# vds_botboard_revB.net
KiCad netlist of a schematic drawn in EAGLE
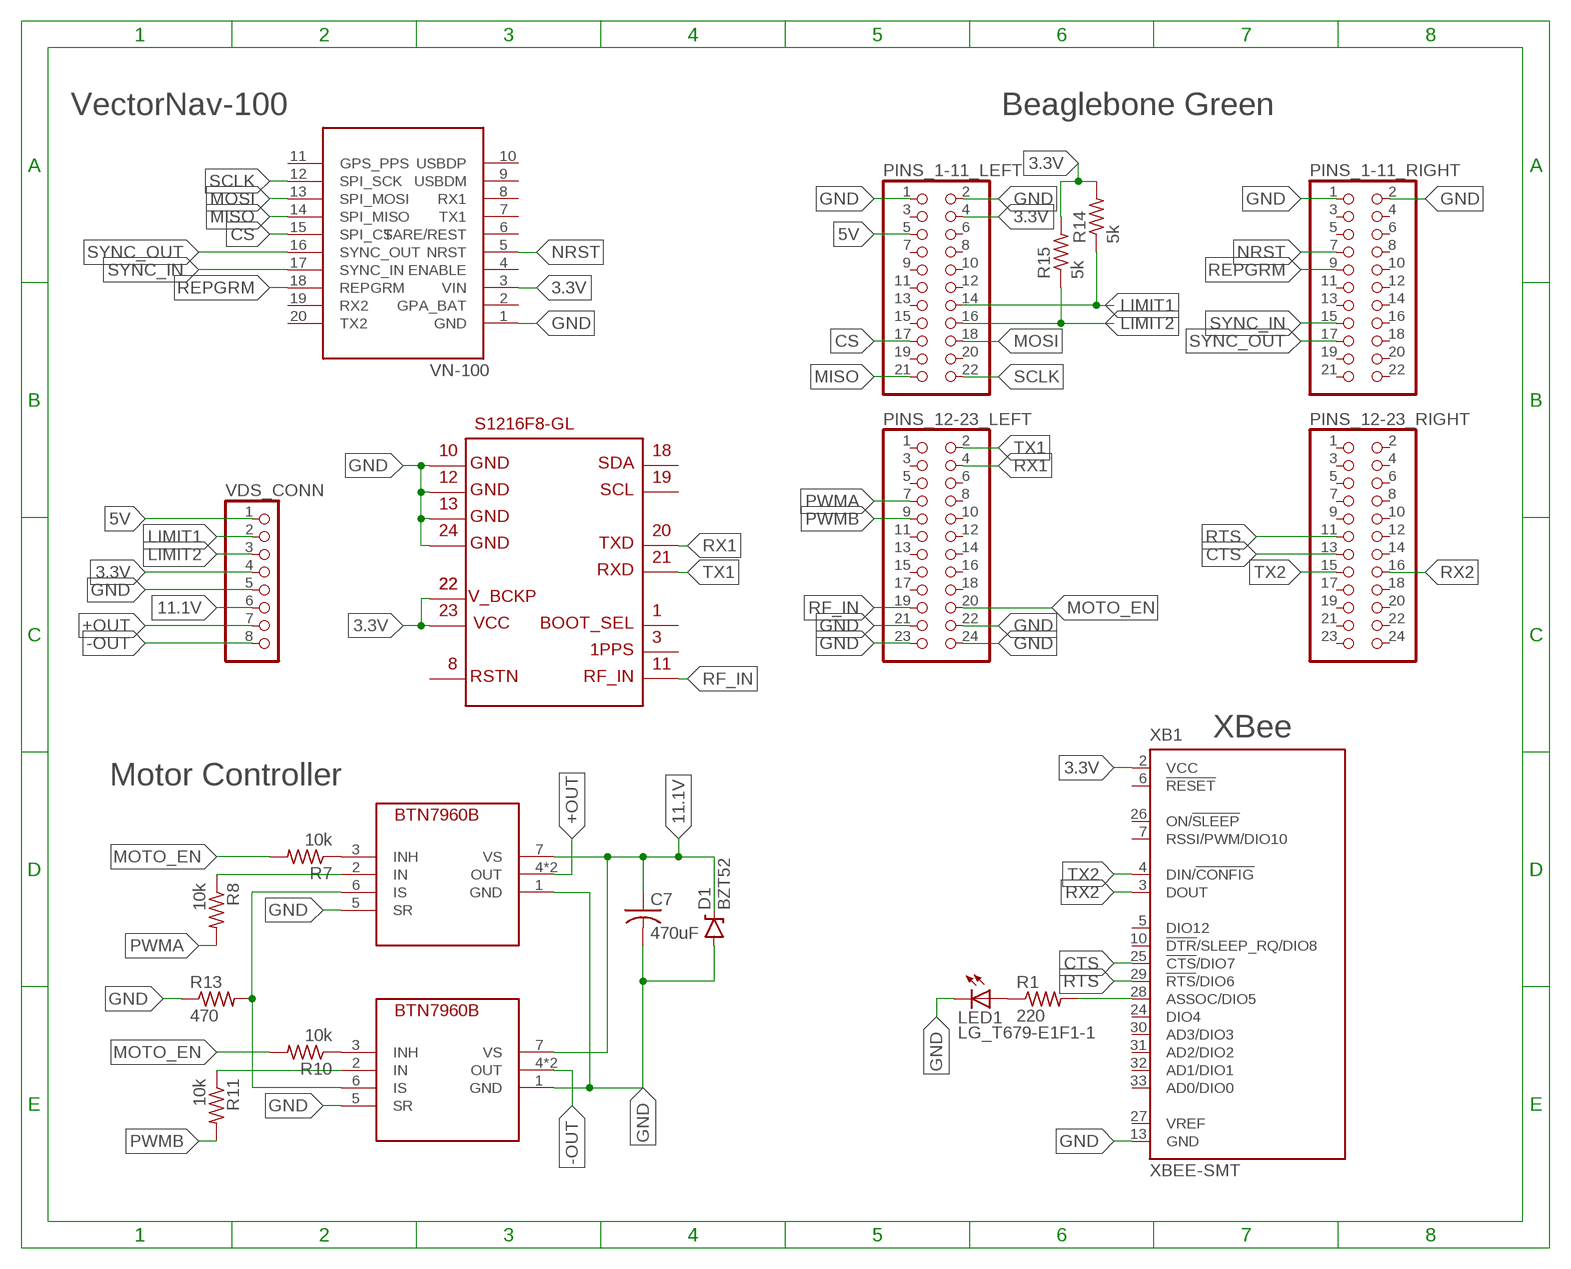
[diagram p0: schematic, sheet 1]

(export (version "E")
  (design (tool "Eeschema 10.0.6"))
  (components
    (comp (ref "C7")
      (value "470uF")
      (footprint "eagle-import:C050-024X044")
      (libsource (lib "eagle-import") (part "C-US050-024X044"))
    )
    (comp (ref "D1")
      (value "BZT52")
      (footprint "eagle-import:DIODE-BZT52")
      (libsource (lib "eagle-import") (part "DIODE-ZENER"))
    )
    (comp (ref "JM1")
      (value "S1216F8-GL")
      (footprint "eagle-import:S1216F8-GL")
      (libsource (lib "eagle-import") (part "S1216F8-GL"))
    )
    (comp (ref "LED1")
      (value "LG_T679-E1F1-1")
      (footprint "eagle-import:PLCC2")
      (libsource (lib "eagle-import") (part "_T679-?-1E1F1LG"))
    )
    (comp (ref "PINS_1-11_LEFT")
      (value "PINHD-2X11")
      (footprint "eagle-import:2X11")
      (libsource (lib "eagle-import") (part "PINHD-2X11"))
    )
    (comp (ref "PINS_1-11_RIGHT")
      (value "PINHD-2X11")
      (footprint "eagle-import:2X11")
      (libsource (lib "eagle-import") (part "PINHD-2X11"))
    )
    (comp (ref "PINS_12-23_LEFT")
      (value "PINHD-2X12")
      (footprint "eagle-import:2X12")
      (libsource (lib "eagle-import") (part "PINHD-2X12"))
    )
    (comp (ref "PINS_12-23_RIGHT")
      (value "PINHD-2X12")
      (footprint "eagle-import:2X12")
      (libsource (lib "eagle-import") (part "PINHD-2X12"))
    )
    (comp (ref "R1")
      (value "220")
      (footprint "eagle-import:0204_5")
      (libsource (lib "eagle-import") (part "resistor_348_R-US_0204/5"))
    )
    (comp (ref "R7")
      (value "10k")
      (footprint "eagle-import:0204_5")
      (libsource (lib "eagle-import") (part "R-US_0204/5"))
    )
    (comp (ref "R8")
      (value "10k")
      (footprint "eagle-import:0204_5")
      (libsource (lib "eagle-import") (part "R-US_0204/5"))
    )
    (comp (ref "R10")
      (value "10k")
      (footprint "eagle-import:0204_5")
      (libsource (lib "eagle-import") (part "R-US_0204/5"))
    )
    (comp (ref "R11")
      (value "10k")
      (footprint "eagle-import:0204_5")
      (libsource (lib "eagle-import") (part "R-US_0204/5"))
    )
    (comp (ref "R13")
      (value "470")
      (footprint "eagle-import:0204_5")
      (libsource (lib "eagle-import") (part "R-US_0204/5"))
    )
    (comp (ref "R14")
      (value "5k")
      (footprint "eagle-import:0204_5")
      (libsource (lib "eagle-import") (part "R-US_0204/5"))
    )
    (comp (ref "R15")
      (value "5k")
      (footprint "eagle-import:0204_5")
      (libsource (lib "eagle-import") (part "R-US_0204/5"))
    )
    (comp (ref "U1")
      (value "INF-PG-TO263-7-1_L_1_BTN7960B")
      (footprint "eagle-import:INF-PG-TO263-7-1_L_1PRIMARY")
      (libsource (lib "eagle-import") (part "INF-PG-TO263-7-1_L_1_BTN7960B"))
    )
    (comp (ref "U2")
      (value "INF-PG-TO263-7-1_L_1_BTN7960B")
      (footprint "eagle-import:INF-PG-TO263-7-1_L_1PRIMARY")
      (libsource (lib "eagle-import") (part "INF-PG-TO263-7-1_L_1_BTN7960B"))
    )
    (comp (ref "VDS_CONN")
      (value "PINHD-1X8")
      (footprint "eagle-import:1X08")
      (libsource (lib "eagle-import") (part "PINHD-1X8"))
    )
    (comp (ref "VN1")
      (value "VECTORNAV-100")
      (footprint "eagle-import:VN-100")
      (libsource (lib "eagle-import") (part "VECTORNAV-100"))
    )
    (comp (ref "XB1")
      (value "XBEE-SMT")
      (footprint "eagle-import:XBEE-SMT")
      (libsource (lib "eagle-import") (part "XBEE-SMT"))
    )
  )
  (nets
    (net (code "1") (name "+OUT") (class "Default")
      (node (ref "U1") (pin "4") (pinfunction "OUT_4") (pintype "bidirectional"))
      (node (ref "U1") (pin "8") (pinfunction "OUT_8") (pintype "bidirectional"))
      (node (ref "VDS_CONN") (pin "7") (pinfunction "7_7") (pintype "passive"))
    )
    (net (code "2") (name "-OUT") (class "Default")
      (node (ref "U2") (pin "4") (pinfunction "OUT_4") (pintype "bidirectional"))
      (node (ref "U2") (pin "8") (pinfunction "OUT_8") (pintype "bidirectional"))
      (node (ref "VDS_CONN") (pin "8") (pinfunction "8_8") (pintype "passive"))
    )
    (net (code "3") (name "3.3V") (class "Default")
      (node (ref "JM1") (pin "22") (pinfunction "22_22") (pintype "bidirectional"))
      (node (ref "JM1") (pin "23") (pinfunction "23_23") (pintype "bidirectional"))
      (node (ref "PINS_1-11_LEFT") (pin "4") (pinfunction "4_4") (pintype "passive"))
      (node (ref "R14") (pin "2") (pinfunction "2_2") (pintype "passive"))
      (node (ref "R15") (pin "2") (pinfunction "2_2") (pintype "passive"))
      (node (ref "VDS_CONN") (pin "4") (pinfunction "4_4") (pintype "passive"))
      (node (ref "VN1") (pin "3") (pinfunction "VIN_3") (pintype "bidirectional"))
      (node (ref "XB1") (pin "2") (pinfunction "VCC_2") (pintype "power_in"))
    )
    (net (code "4") (name "5V") (class "Default")
      (node (ref "PINS_1-11_LEFT") (pin "5") (pinfunction "5_5") (pintype "passive"))
      (node (ref "VDS_CONN") (pin "1") (pinfunction "1_1") (pintype "passive"))
    )
    (net (code "5") (name "11.1V") (class "Default")
      (node (ref "C7") (pin "1") (pinfunction "1_1") (pintype "passive"))
      (node (ref "D1") (pin "C") (pinfunction "C_C") (pintype "passive"))
      (node (ref "U1") (pin "7") (pinfunction "VS_7") (pintype "bidirectional"))
      (node (ref "U2") (pin "7") (pinfunction "VS_7") (pintype "bidirectional"))
      (node (ref "VDS_CONN") (pin "6") (pinfunction "6_6") (pintype "passive"))
    )
    (net (code "6") (name "CS") (class "Default")
      (node (ref "PINS_1-11_LEFT") (pin "17") (pinfunction "17_17") (pintype "passive"))
      (node (ref "VN1") (pin "15") (pinfunction "SPI_CS_15") (pintype "bidirectional"))
    )
    (net (code "7") (name "CTS") (class "Default")
      (node (ref "PINS_12-23_RIGHT") (pin "13") (pinfunction "13_13") (pintype "passive"))
      (node (ref "XB1") (pin "25") (pinfunction "~{CTS}/DIO7_25") (pintype "bidirectional"))
    )
    (net (code "8") (name "GND") (class "Default")
      (node (ref "C7") (pin "2") (pinfunction "2_2") (pintype "passive"))
      (node (ref "D1") (pin "A") (pinfunction "A_A") (pintype "passive"))
      (node (ref "JM1") (pin "10") (pinfunction "10_10") (pintype "bidirectional"))
      (node (ref "JM1") (pin "12") (pinfunction "12_12") (pintype "bidirectional"))
      (node (ref "JM1") (pin "13") (pinfunction "13_13") (pintype "bidirectional"))
      (node (ref "JM1") (pin "24") (pinfunction "24_24") (pintype "bidirectional"))
      (node (ref "LED1") (pin "C") (pinfunction "C_C") (pintype "passive"))
      (node (ref "PINS_1-11_LEFT") (pin "1") (pinfunction "1_1") (pintype "passive"))
      (node (ref "PINS_1-11_LEFT") (pin "2") (pinfunction "2_2") (pintype "passive"))
      (node (ref "PINS_1-11_RIGHT") (pin "1") (pinfunction "1_1") (pintype "passive"))
      (node (ref "PINS_1-11_RIGHT") (pin "2") (pinfunction "2_2") (pintype "passive"))
      (node (ref "PINS_12-23_LEFT") (pin "21") (pinfunction "21_21") (pintype "passive"))
      (node (ref "PINS_12-23_LEFT") (pin "22") (pinfunction "22_22") (pintype "passive"))
      (node (ref "PINS_12-23_LEFT") (pin "23") (pinfunction "23_23") (pintype "passive"))
      (node (ref "PINS_12-23_LEFT") (pin "24") (pinfunction "24_24") (pintype "passive"))
      (node (ref "R13") (pin "1") (pinfunction "1_1") (pintype "passive"))
      (node (ref "U1") (pin "1") (pinfunction "GND_1") (pintype "bidirectional"))
      (node (ref "U1") (pin "5") (pinfunction "SR_5") (pintype "bidirectional"))
      (node (ref "U2") (pin "1") (pinfunction "GND_1") (pintype "bidirectional"))
      (node (ref "U2") (pin "5") (pinfunction "SR_5") (pintype "bidirectional"))
      (node (ref "VDS_CONN") (pin "5") (pinfunction "5_5") (pintype "passive"))
      (node (ref "VN1") (pin "1") (pinfunction "GND_1") (pintype "bidirectional"))
      (node (ref "XB1") (pin "13") (pinfunction "GND_13") (pintype "power_in"))
    )
    (net (code "9") (name "LIMIT1") (class "Default")
      (node (ref "PINS_1-11_LEFT") (pin "14") (pinfunction "14_14") (pintype "passive"))
      (node (ref "R14") (pin "1") (pinfunction "1_1") (pintype "passive"))
      (node (ref "VDS_CONN") (pin "2") (pinfunction "2_2") (pintype "passive"))
    )
    (net (code "10") (name "LIMIT2") (class "Default")
      (node (ref "PINS_1-11_LEFT") (pin "16") (pinfunction "16_16") (pintype "passive"))
      (node (ref "R15") (pin "1") (pinfunction "1_1") (pintype "passive"))
      (node (ref "VDS_CONN") (pin "3") (pinfunction "3_3") (pintype "passive"))
    )
    (net (code "11") (name "MISO") (class "Default")
      (node (ref "PINS_1-11_LEFT") (pin "21") (pinfunction "21_21") (pintype "passive"))
      (node (ref "VN1") (pin "14") (pinfunction "SPI_MISO_14") (pintype "bidirectional"))
    )
    (net (code "12") (name "MOSI") (class "Default")
      (node (ref "PINS_1-11_LEFT") (pin "18") (pinfunction "18_18") (pintype "passive"))
      (node (ref "VN1") (pin "13") (pinfunction "SPI_MOSI_13") (pintype "bidirectional"))
    )
    (net (code "13") (name "MOTO_EN") (class "Default")
      (node (ref "PINS_12-23_LEFT") (pin "20") (pinfunction "20_20") (pintype "passive"))
      (node (ref "R10") (pin "2") (pinfunction "2_2") (pintype "passive"))
      (node (ref "R7") (pin "2") (pinfunction "2_2") (pintype "passive"))
    )
    (net (code "14") (name "NRST") (class "Default")
      (node (ref "PINS_1-11_RIGHT") (pin "7") (pinfunction "7_7") (pintype "passive"))
      (node (ref "VN1") (pin "5") (pinfunction "NRST_5") (pintype "bidirectional"))
    )
    (net (code "15") (name "Net-(LED1-PadA)") (class "Default")
      (node (ref "LED1") (pin "A") (pinfunction "A_A") (pintype "passive"))
      (node (ref "R1") (pin "1") (pinfunction "1_1") (pintype "passive"))
    )
    (net (code "16") (name "Net-(U1-IN)") (class "Default")
      (node (ref "R8") (pin "1") (pinfunction "1_1") (pintype "passive"))
      (node (ref "U1") (pin "2") (pinfunction "IN_2") (pintype "bidirectional"))
    )
    (net (code "17") (name "Net-(U1-INH)") (class "Default")
      (node (ref "R7") (pin "1") (pinfunction "1_1") (pintype "passive"))
      (node (ref "U1") (pin "3") (pinfunction "INH_3") (pintype "bidirectional"))
    )
    (net (code "18") (name "Net-(U1-IS)") (class "Default")
      (node (ref "R13") (pin "2") (pinfunction "2_2") (pintype "passive"))
      (node (ref "U1") (pin "6") (pinfunction "IS_6") (pintype "bidirectional"))
      (node (ref "U2") (pin "6") (pinfunction "IS_6") (pintype "bidirectional"))
    )
    (net (code "19") (name "Net-(U2-IN)") (class "Default")
      (node (ref "R11") (pin "1") (pinfunction "1_1") (pintype "passive"))
      (node (ref "U2") (pin "2") (pinfunction "IN_2") (pintype "bidirectional"))
    )
    (net (code "20") (name "Net-(U2-INH)") (class "Default")
      (node (ref "R10") (pin "1") (pinfunction "1_1") (pintype "passive"))
      (node (ref "U2") (pin "3") (pinfunction "INH_3") (pintype "bidirectional"))
    )
    (net (code "21") (name "Net-(XB1-ASSOC{slash}DIO5)") (class "Default")
      (node (ref "R1") (pin "2") (pinfunction "2_2") (pintype "passive"))
      (node (ref "XB1") (pin "28") (pinfunction "ASSOC/DIO5_28") (pintype "bidirectional"))
    )
    (net (code "22") (name "PWMA") (class "Default")
      (node (ref "PINS_12-23_LEFT") (pin "7") (pinfunction "7_7") (pintype "passive"))
      (node (ref "R8") (pin "2") (pinfunction "2_2") (pintype "passive"))
    )
    (net (code "23") (name "PWMB") (class "Default")
      (node (ref "PINS_12-23_LEFT") (pin "9") (pinfunction "9_9") (pintype "passive"))
      (node (ref "R11") (pin "2") (pinfunction "2_2") (pintype "passive"))
    )
    (net (code "24") (name "REPGRM") (class "Default")
      (node (ref "PINS_1-11_RIGHT") (pin "9") (pinfunction "9_9") (pintype "passive"))
      (node (ref "VN1") (pin "18") (pinfunction "REPGRM_18") (pintype "bidirectional"))
    )
    (net (code "25") (name "RF_IN") (class "Default")
      (node (ref "JM1") (pin "11") (pinfunction "11_11") (pintype "bidirectional"))
      (node (ref "PINS_12-23_LEFT") (pin "19") (pinfunction "19_19") (pintype "passive"))
    )
    (net (code "26") (name "RTS") (class "Default")
      (node (ref "PINS_12-23_RIGHT") (pin "11") (pinfunction "11_11") (pintype "passive"))
      (node (ref "XB1") (pin "29") (pinfunction "~{RTS}/DIO6_29") (pintype "bidirectional"))
    )
    (net (code "27") (name "RX1") (class "Default")
      (node (ref "JM1") (pin "20") (pinfunction "20_20") (pintype "bidirectional"))
      (node (ref "PINS_12-23_LEFT") (pin "4") (pinfunction "4_4") (pintype "passive"))
    )
    (net (code "28") (name "RX2") (class "Default")
      (node (ref "PINS_12-23_RIGHT") (pin "16") (pinfunction "16_16") (pintype "passive"))
      (node (ref "XB1") (pin "3") (pinfunction "DOUT_3") (pintype "output"))
    )
    (net (code "29") (name "SCLK") (class "Default")
      (node (ref "PINS_1-11_LEFT") (pin "22") (pinfunction "22_22") (pintype "passive"))
      (node (ref "VN1") (pin "12") (pinfunction "SPI_SCK_12") (pintype "bidirectional"))
    )
    (net (code "30") (name "SYNC_IN") (class "Default")
      (node (ref "PINS_1-11_RIGHT") (pin "15") (pinfunction "15_15") (pintype "passive"))
      (node (ref "VN1") (pin "17") (pinfunction "SYNC_IN_17") (pintype "bidirectional"))
    )
    (net (code "31") (name "SYNC_OUT") (class "Default")
      (node (ref "PINS_1-11_RIGHT") (pin "17") (pinfunction "17_17") (pintype "passive"))
      (node (ref "VN1") (pin "16") (pinfunction "SYNC_OUT_16") (pintype "bidirectional"))
    )
    (net (code "32") (name "TX1") (class "Default")
      (node (ref "JM1") (pin "21") (pinfunction "21_21") (pintype "bidirectional"))
      (node (ref "PINS_12-23_LEFT") (pin "2") (pinfunction "2_2") (pintype "passive"))
    )
    (net (code "33") (name "TX2") (class "Default")
      (node (ref "PINS_12-23_RIGHT") (pin "15") (pinfunction "15_15") (pintype "passive"))
      (node (ref "XB1") (pin "4") (pinfunction "DIN/~{CONFIG}_4") (pintype "input"))
    )
    (net (code "34") (name "unconnected-(JM1-Pad1)") (class "Default")
      (node (ref "JM1") (pin "1") (pinfunction "1_1") (pintype "bidirectional"))
    )
    (net (code "35") (name "unconnected-(JM1-Pad3)") (class "Default")
      (node (ref "JM1") (pin "3") (pinfunction "3_3") (pintype "bidirectional"))
    )
    (net (code "36") (name "unconnected-(JM1-Pad8)") (class "Default")
      (node (ref "JM1") (pin "8") (pinfunction "8_8") (pintype "bidirectional"))
    )
    (net (code "37") (name "unconnected-(JM1-Pad18)") (class "Default")
      (node (ref "JM1") (pin "18") (pinfunction "18_18") (pintype "bidirectional"))
    )
    (net (code "38") (name "unconnected-(JM1-Pad19)") (class "Default")
      (node (ref "JM1") (pin "19") (pinfunction "19_19") (pintype "bidirectional"))
    )
    (net (code "39") (name "unconnected-(PINS_1-11_LEFT-Pad3)") (class "Default")
      (node (ref "PINS_1-11_LEFT") (pin "3") (pinfunction "3_3") (pintype "passive"))
    )
    (net (code "40") (name "unconnected-(PINS_1-11_LEFT-Pad6)") (class "Default")
      (node (ref "PINS_1-11_LEFT") (pin "6") (pinfunction "6_6") (pintype "passive"))
    )
    (net (code "41") (name "unconnected-(PINS_1-11_LEFT-Pad7)") (class "Default")
      (node (ref "PINS_1-11_LEFT") (pin "7") (pinfunction "7_7") (pintype "passive"))
    )
    (net (code "42") (name "unconnected-(PINS_1-11_LEFT-Pad8)") (class "Default")
      (node (ref "PINS_1-11_LEFT") (pin "8") (pinfunction "8_8") (pintype "passive"))
    )
    (net (code "43") (name "unconnected-(PINS_1-11_LEFT-Pad9)") (class "Default")
      (node (ref "PINS_1-11_LEFT") (pin "9") (pinfunction "9_9") (pintype "passive"))
    )
    (net (code "44") (name "unconnected-(PINS_1-11_LEFT-Pad10)") (class "Default")
      (node (ref "PINS_1-11_LEFT") (pin "10") (pinfunction "10_10") (pintype "passive"))
    )
    (net (code "45") (name "unconnected-(PINS_1-11_LEFT-Pad11)") (class "Default")
      (node (ref "PINS_1-11_LEFT") (pin "11") (pinfunction "11_11") (pintype "passive"))
    )
    (net (code "46") (name "unconnected-(PINS_1-11_LEFT-Pad12)") (class "Default")
      (node (ref "PINS_1-11_LEFT") (pin "12") (pinfunction "12_12") (pintype "passive"))
    )
    (net (code "47") (name "unconnected-(PINS_1-11_LEFT-Pad13)") (class "Default")
      (node (ref "PINS_1-11_LEFT") (pin "13") (pinfunction "13_13") (pintype "passive"))
    )
    (net (code "48") (name "unconnected-(PINS_1-11_LEFT-Pad15)") (class "Default")
      (node (ref "PINS_1-11_LEFT") (pin "15") (pinfunction "15_15") (pintype "passive"))
    )
    (net (code "49") (name "unconnected-(PINS_1-11_LEFT-Pad19)") (class "Default")
      (node (ref "PINS_1-11_LEFT") (pin "19") (pinfunction "19_19") (pintype "passive"))
    )
    (net (code "50") (name "unconnected-(PINS_1-11_LEFT-Pad20)") (class "Default")
      (node (ref "PINS_1-11_LEFT") (pin "20") (pinfunction "20_20") (pintype "passive"))
    )
    (net (code "51") (name "unconnected-(PINS_1-11_RIGHT-Pad3)") (class "Default")
      (node (ref "PINS_1-11_RIGHT") (pin "3") (pinfunction "3_3") (pintype "passive"))
    )
    (net (code "52") (name "unconnected-(PINS_1-11_RIGHT-Pad4)") (class "Default")
      (node (ref "PINS_1-11_RIGHT") (pin "4") (pinfunction "4_4") (pintype "passive"))
    )
    (net (code "53") (name "unconnected-(PINS_1-11_RIGHT-Pad5)") (class "Default")
      (node (ref "PINS_1-11_RIGHT") (pin "5") (pinfunction "5_5") (pintype "passive"))
    )
    (net (code "54") (name "unconnected-(PINS_1-11_RIGHT-Pad6)") (class "Default")
      (node (ref "PINS_1-11_RIGHT") (pin "6") (pinfunction "6_6") (pintype "passive"))
    )
    (net (code "55") (name "unconnected-(PINS_1-11_RIGHT-Pad8)") (class "Default")
      (node (ref "PINS_1-11_RIGHT") (pin "8") (pinfunction "8_8") (pintype "passive"))
    )
    (net (code "56") (name "unconnected-(PINS_1-11_RIGHT-Pad10)") (class "Default")
      (node (ref "PINS_1-11_RIGHT") (pin "10") (pinfunction "10_10") (pintype "passive"))
    )
    (net (code "57") (name "unconnected-(PINS_1-11_RIGHT-Pad11)") (class "Default")
      (node (ref "PINS_1-11_RIGHT") (pin "11") (pinfunction "11_11") (pintype "passive"))
    )
    (net (code "58") (name "unconnected-(PINS_1-11_RIGHT-Pad12)") (class "Default")
      (node (ref "PINS_1-11_RIGHT") (pin "12") (pinfunction "12_12") (pintype "passive"))
    )
    (net (code "59") (name "unconnected-(PINS_1-11_RIGHT-Pad13)") (class "Default")
      (node (ref "PINS_1-11_RIGHT") (pin "13") (pinfunction "13_13") (pintype "passive"))
    )
    (net (code "60") (name "unconnected-(PINS_1-11_RIGHT-Pad14)") (class "Default")
      (node (ref "PINS_1-11_RIGHT") (pin "14") (pinfunction "14_14") (pintype "passive"))
    )
    (net (code "61") (name "unconnected-(PINS_1-11_RIGHT-Pad16)") (class "Default")
      (node (ref "PINS_1-11_RIGHT") (pin "16") (pinfunction "16_16") (pintype "passive"))
    )
    (net (code "62") (name "unconnected-(PINS_1-11_RIGHT-Pad18)") (class "Default")
      (node (ref "PINS_1-11_RIGHT") (pin "18") (pinfunction "18_18") (pintype "passive"))
    )
    (net (code "63") (name "unconnected-(PINS_1-11_RIGHT-Pad19)") (class "Default")
      (node (ref "PINS_1-11_RIGHT") (pin "19") (pinfunction "19_19") (pintype "passive"))
    )
    (net (code "64") (name "unconnected-(PINS_1-11_RIGHT-Pad20)") (class "Default")
      (node (ref "PINS_1-11_RIGHT") (pin "20") (pinfunction "20_20") (pintype "passive"))
    )
    (net (code "65") (name "unconnected-(PINS_1-11_RIGHT-Pad21)") (class "Default")
      (node (ref "PINS_1-11_RIGHT") (pin "21") (pinfunction "21_21") (pintype "passive"))
    )
    (net (code "66") (name "unconnected-(PINS_1-11_RIGHT-Pad22)") (class "Default")
      (node (ref "PINS_1-11_RIGHT") (pin "22") (pinfunction "22_22") (pintype "passive"))
    )
    (net (code "67") (name "unconnected-(PINS_12-23_LEFT-Pad1)") (class "Default")
      (node (ref "PINS_12-23_LEFT") (pin "1") (pinfunction "1_1") (pintype "passive"))
    )
    (net (code "68") (name "unconnected-(PINS_12-23_LEFT-Pad3)") (class "Default")
      (node (ref "PINS_12-23_LEFT") (pin "3") (pinfunction "3_3") (pintype "passive"))
    )
    (net (code "69") (name "unconnected-(PINS_12-23_LEFT-Pad5)") (class "Default")
      (node (ref "PINS_12-23_LEFT") (pin "5") (pinfunction "5_5") (pintype "passive"))
    )
    (net (code "70") (name "unconnected-(PINS_12-23_LEFT-Pad6)") (class "Default")
      (node (ref "PINS_12-23_LEFT") (pin "6") (pinfunction "6_6") (pintype "passive"))
    )
    (net (code "71") (name "unconnected-(PINS_12-23_LEFT-Pad8)") (class "Default")
      (node (ref "PINS_12-23_LEFT") (pin "8") (pinfunction "8_8") (pintype "passive"))
    )
    (net (code "72") (name "unconnected-(PINS_12-23_LEFT-Pad10)") (class "Default")
      (node (ref "PINS_12-23_LEFT") (pin "10") (pinfunction "10_10") (pintype "passive"))
    )
    (net (code "73") (name "unconnected-(PINS_12-23_LEFT-Pad11)") (class "Default")
      (node (ref "PINS_12-23_LEFT") (pin "11") (pinfunction "11_11") (pintype "passive"))
    )
    (net (code "74") (name "unconnected-(PINS_12-23_LEFT-Pad12)") (class "Default")
      (node (ref "PINS_12-23_LEFT") (pin "12") (pinfunction "12_12") (pintype "passive"))
    )
    (net (code "75") (name "unconnected-(PINS_12-23_LEFT-Pad13)") (class "Default")
      (node (ref "PINS_12-23_LEFT") (pin "13") (pinfunction "13_13") (pintype "passive"))
    )
    (net (code "76") (name "unconnected-(PINS_12-23_LEFT-Pad14)") (class "Default")
      (node (ref "PINS_12-23_LEFT") (pin "14") (pinfunction "14_14") (pintype "passive"))
    )
    (net (code "77") (name "unconnected-(PINS_12-23_LEFT-Pad15)") (class "Default")
      (node (ref "PINS_12-23_LEFT") (pin "15") (pinfunction "15_15") (pintype "passive"))
    )
    (net (code "78") (name "unconnected-(PINS_12-23_LEFT-Pad16)") (class "Default")
      (node (ref "PINS_12-23_LEFT") (pin "16") (pinfunction "16_16") (pintype "passive"))
    )
    (net (code "79") (name "unconnected-(PINS_12-23_LEFT-Pad17)") (class "Default")
      (node (ref "PINS_12-23_LEFT") (pin "17") (pinfunction "17_17") (pintype "passive"))
    )
    (net (code "80") (name "unconnected-(PINS_12-23_LEFT-Pad18)") (class "Default")
      (node (ref "PINS_12-23_LEFT") (pin "18") (pinfunction "18_18") (pintype "passive"))
    )
    (net (code "81") (name "unconnected-(PINS_12-23_RIGHT-Pad1)") (class "Default")
      (node (ref "PINS_12-23_RIGHT") (pin "1") (pinfunction "1_1") (pintype "passive"))
    )
    (net (code "82") (name "unconnected-(PINS_12-23_RIGHT-Pad2)") (class "Default")
      (node (ref "PINS_12-23_RIGHT") (pin "2") (pinfunction "2_2") (pintype "passive"))
    )
    (net (code "83") (name "unconnected-(PINS_12-23_RIGHT-Pad3)") (class "Default")
      (node (ref "PINS_12-23_RIGHT") (pin "3") (pinfunction "3_3") (pintype "passive"))
    )
    (net (code "84") (name "unconnected-(PINS_12-23_RIGHT-Pad4)") (class "Default")
      (node (ref "PINS_12-23_RIGHT") (pin "4") (pinfunction "4_4") (pintype "passive"))
    )
    (net (code "85") (name "unconnected-(PINS_12-23_RIGHT-Pad5)") (class "Default")
      (node (ref "PINS_12-23_RIGHT") (pin "5") (pinfunction "5_5") (pintype "passive"))
    )
    (net (code "86") (name "unconnected-(PINS_12-23_RIGHT-Pad6)") (class "Default")
      (node (ref "PINS_12-23_RIGHT") (pin "6") (pinfunction "6_6") (pintype "passive"))
    )
    (net (code "87") (name "unconnected-(PINS_12-23_RIGHT-Pad7)") (class "Default")
      (node (ref "PINS_12-23_RIGHT") (pin "7") (pinfunction "7_7") (pintype "passive"))
    )
    (net (code "88") (name "unconnected-(PINS_12-23_RIGHT-Pad8)") (class "Default")
      (node (ref "PINS_12-23_RIGHT") (pin "8") (pinfunction "8_8") (pintype "passive"))
    )
    (net (code "89") (name "unconnected-(PINS_12-23_RIGHT-Pad9)") (class "Default")
      (node (ref "PINS_12-23_RIGHT") (pin "9") (pinfunction "9_9") (pintype "passive"))
    )
    (net (code "90") (name "unconnected-(PINS_12-23_RIGHT-Pad10)") (class "Default")
      (node (ref "PINS_12-23_RIGHT") (pin "10") (pinfunction "10_10") (pintype "passive"))
    )
    (net (code "91") (name "unconnected-(PINS_12-23_RIGHT-Pad12)") (class "Default")
      (node (ref "PINS_12-23_RIGHT") (pin "12") (pinfunction "12_12") (pintype "passive"))
    )
    (net (code "92") (name "unconnected-(PINS_12-23_RIGHT-Pad14)") (class "Default")
      (node (ref "PINS_12-23_RIGHT") (pin "14") (pinfunction "14_14") (pintype "passive"))
    )
    (net (code "93") (name "unconnected-(PINS_12-23_RIGHT-Pad17)") (class "Default")
      (node (ref "PINS_12-23_RIGHT") (pin "17") (pinfunction "17_17") (pintype "passive"))
    )
    (net (code "94") (name "unconnected-(PINS_12-23_RIGHT-Pad18)") (class "Default")
      (node (ref "PINS_12-23_RIGHT") (pin "18") (pinfunction "18_18") (pintype "passive"))
    )
    (net (code "95") (name "unconnected-(PINS_12-23_RIGHT-Pad19)") (class "Default")
      (node (ref "PINS_12-23_RIGHT") (pin "19") (pinfunction "19_19") (pintype "passive"))
    )
    (net (code "96") (name "unconnected-(PINS_12-23_RIGHT-Pad20)") (class "Default")
      (node (ref "PINS_12-23_RIGHT") (pin "20") (pinfunction "20_20") (pintype "passive"))
    )
    (net (code "97") (name "unconnected-(PINS_12-23_RIGHT-Pad21)") (class "Default")
      (node (ref "PINS_12-23_RIGHT") (pin "21") (pinfunction "21_21") (pintype "passive"))
    )
    (net (code "98") (name "unconnected-(PINS_12-23_RIGHT-Pad22)") (class "Default")
      (node (ref "PINS_12-23_RIGHT") (pin "22") (pinfunction "22_22") (pintype "passive"))
    )
    (net (code "99") (name "unconnected-(PINS_12-23_RIGHT-Pad23)") (class "Default")
      (node (ref "PINS_12-23_RIGHT") (pin "23") (pinfunction "23_23") (pintype "passive"))
    )
    (net (code "100") (name "unconnected-(PINS_12-23_RIGHT-Pad24)") (class "Default")
      (node (ref "PINS_12-23_RIGHT") (pin "24") (pinfunction "24_24") (pintype "passive"))
    )
    (net (code "101") (name "unconnected-(VN1-ENABLE-Pad4)") (class "Default")
      (node (ref "VN1") (pin "4") (pinfunction "ENABLE_4") (pintype "bidirectional"))
    )
    (net (code "102") (name "unconnected-(VN1-GPA_BAT-Pad2)") (class "Default")
      (node (ref "VN1") (pin "2") (pinfunction "GPA_BAT_2") (pintype "bidirectional"))
    )
    (net (code "103") (name "unconnected-(VN1-GPS_PPS-Pad11)") (class "Default")
      (node (ref "VN1") (pin "11") (pinfunction "GPS_PPS_11") (pintype "bidirectional"))
    )
    (net (code "104") (name "unconnected-(VN1-RX1-Pad8)") (class "Default")
      (node (ref "VN1") (pin "8") (pinfunction "RX1_8") (pintype "bidirectional"))
    )
    (net (code "105") (name "unconnected-(VN1-RX2-Pad19)") (class "Default")
      (node (ref "VN1") (pin "19") (pinfunction "RX2_19") (pintype "bidirectional"))
    )
    (net (code "106") (name "unconnected-(VN1-TARE{slash}REST-Pad6)") (class "Default")
      (node (ref "VN1") (pin "6") (pinfunction "TARE/REST_6") (pintype "bidirectional"))
    )
    (net (code "107") (name "unconnected-(VN1-TX1-Pad7)") (class "Default")
      (node (ref "VN1") (pin "7") (pinfunction "TX1_7") (pintype "bidirectional"))
    )
    (net (code "108") (name "unconnected-(VN1-TX2-Pad20)") (class "Default")
      (node (ref "VN1") (pin "20") (pinfunction "TX2_20") (pintype "bidirectional"))
    )
    (net (code "109") (name "unconnected-(VN1-USBDM-Pad9)") (class "Default")
      (node (ref "VN1") (pin "9") (pinfunction "USBDM_9") (pintype "bidirectional"))
    )
    (net (code "110") (name "unconnected-(VN1-USBDP-Pad10)") (class "Default")
      (node (ref "VN1") (pin "10") (pinfunction "USBDP_10") (pintype "bidirectional"))
    )
    (net (code "111") (name "unconnected-(XB1-AD0{slash}DIO0-Pad33)") (class "Default")
      (node (ref "XB1") (pin "33") (pinfunction "AD0/DIO0_33") (pintype "bidirectional"))
    )
    (net (code "112") (name "unconnected-(XB1-AD1{slash}DIO1-Pad32)") (class "Default")
      (node (ref "XB1") (pin "32") (pinfunction "AD1/DIO1_32") (pintype "bidirectional"))
    )
    (net (code "113") (name "unconnected-(XB1-AD2{slash}DIO2-Pad31)") (class "Default")
      (node (ref "XB1") (pin "31") (pinfunction "AD2/DIO2_31") (pintype "bidirectional"))
    )
    (net (code "114") (name "unconnected-(XB1-AD3{slash}DIO3-Pad30)") (class "Default")
      (node (ref "XB1") (pin "30") (pinfunction "AD3/DIO3_30") (pintype "bidirectional"))
    )
    (net (code "115") (name "unconnected-(XB1-DIO4-Pad24)") (class "Default")
      (node (ref "XB1") (pin "24") (pinfunction "DIO4_24") (pintype "bidirectional"))
    )
    (net (code "116") (name "unconnected-(XB1-DIO12-Pad5)") (class "Default")
      (node (ref "XB1") (pin "5") (pinfunction "DIO12_5") (pintype "bidirectional"))
    )
    (net (code "117") (name "unconnected-(XB1-ON{slash}~{SLEEP}-Pad26)") (class "Default")
      (node (ref "XB1") (pin "26") (pinfunction "ON/~{SLEEP}_26") (pintype "output"))
    )
    (net (code "118") (name "unconnected-(XB1-RSSI{slash}PWM{slash}DIO10-Pad7)") (class "Default")
      (node (ref "XB1") (pin "7") (pinfunction "RSSI/PWM/DIO10_7") (pintype "output"))
    )
    (net (code "119") (name "unconnected-(XB1-VREF-Pad27)") (class "Default")
      (node (ref "XB1") (pin "27") (pinfunction "VREF_27") (pintype "input"))
    )
    (net (code "120") (name "unconnected-(XB1-~{DTR}{slash}SLEEP_RQ{slash}DIO8-Pad10)") (class "Default")
      (node (ref "XB1") (pin "10") (pinfunction "~{DTR}/SLEEP_RQ/DIO8_10") (pintype "bidirectional"))
    )
    (net (code "121") (name "unconnected-(XB1-~{RESET}-Pad6)") (class "Default")
      (node (ref "XB1") (pin "6") (pinfunction "~{RESET}_6") (pintype "input"))
    )
  )
)
